# TrinketBlinkM0F.net
KiCad netlist of a schematic drawn in EAGLE
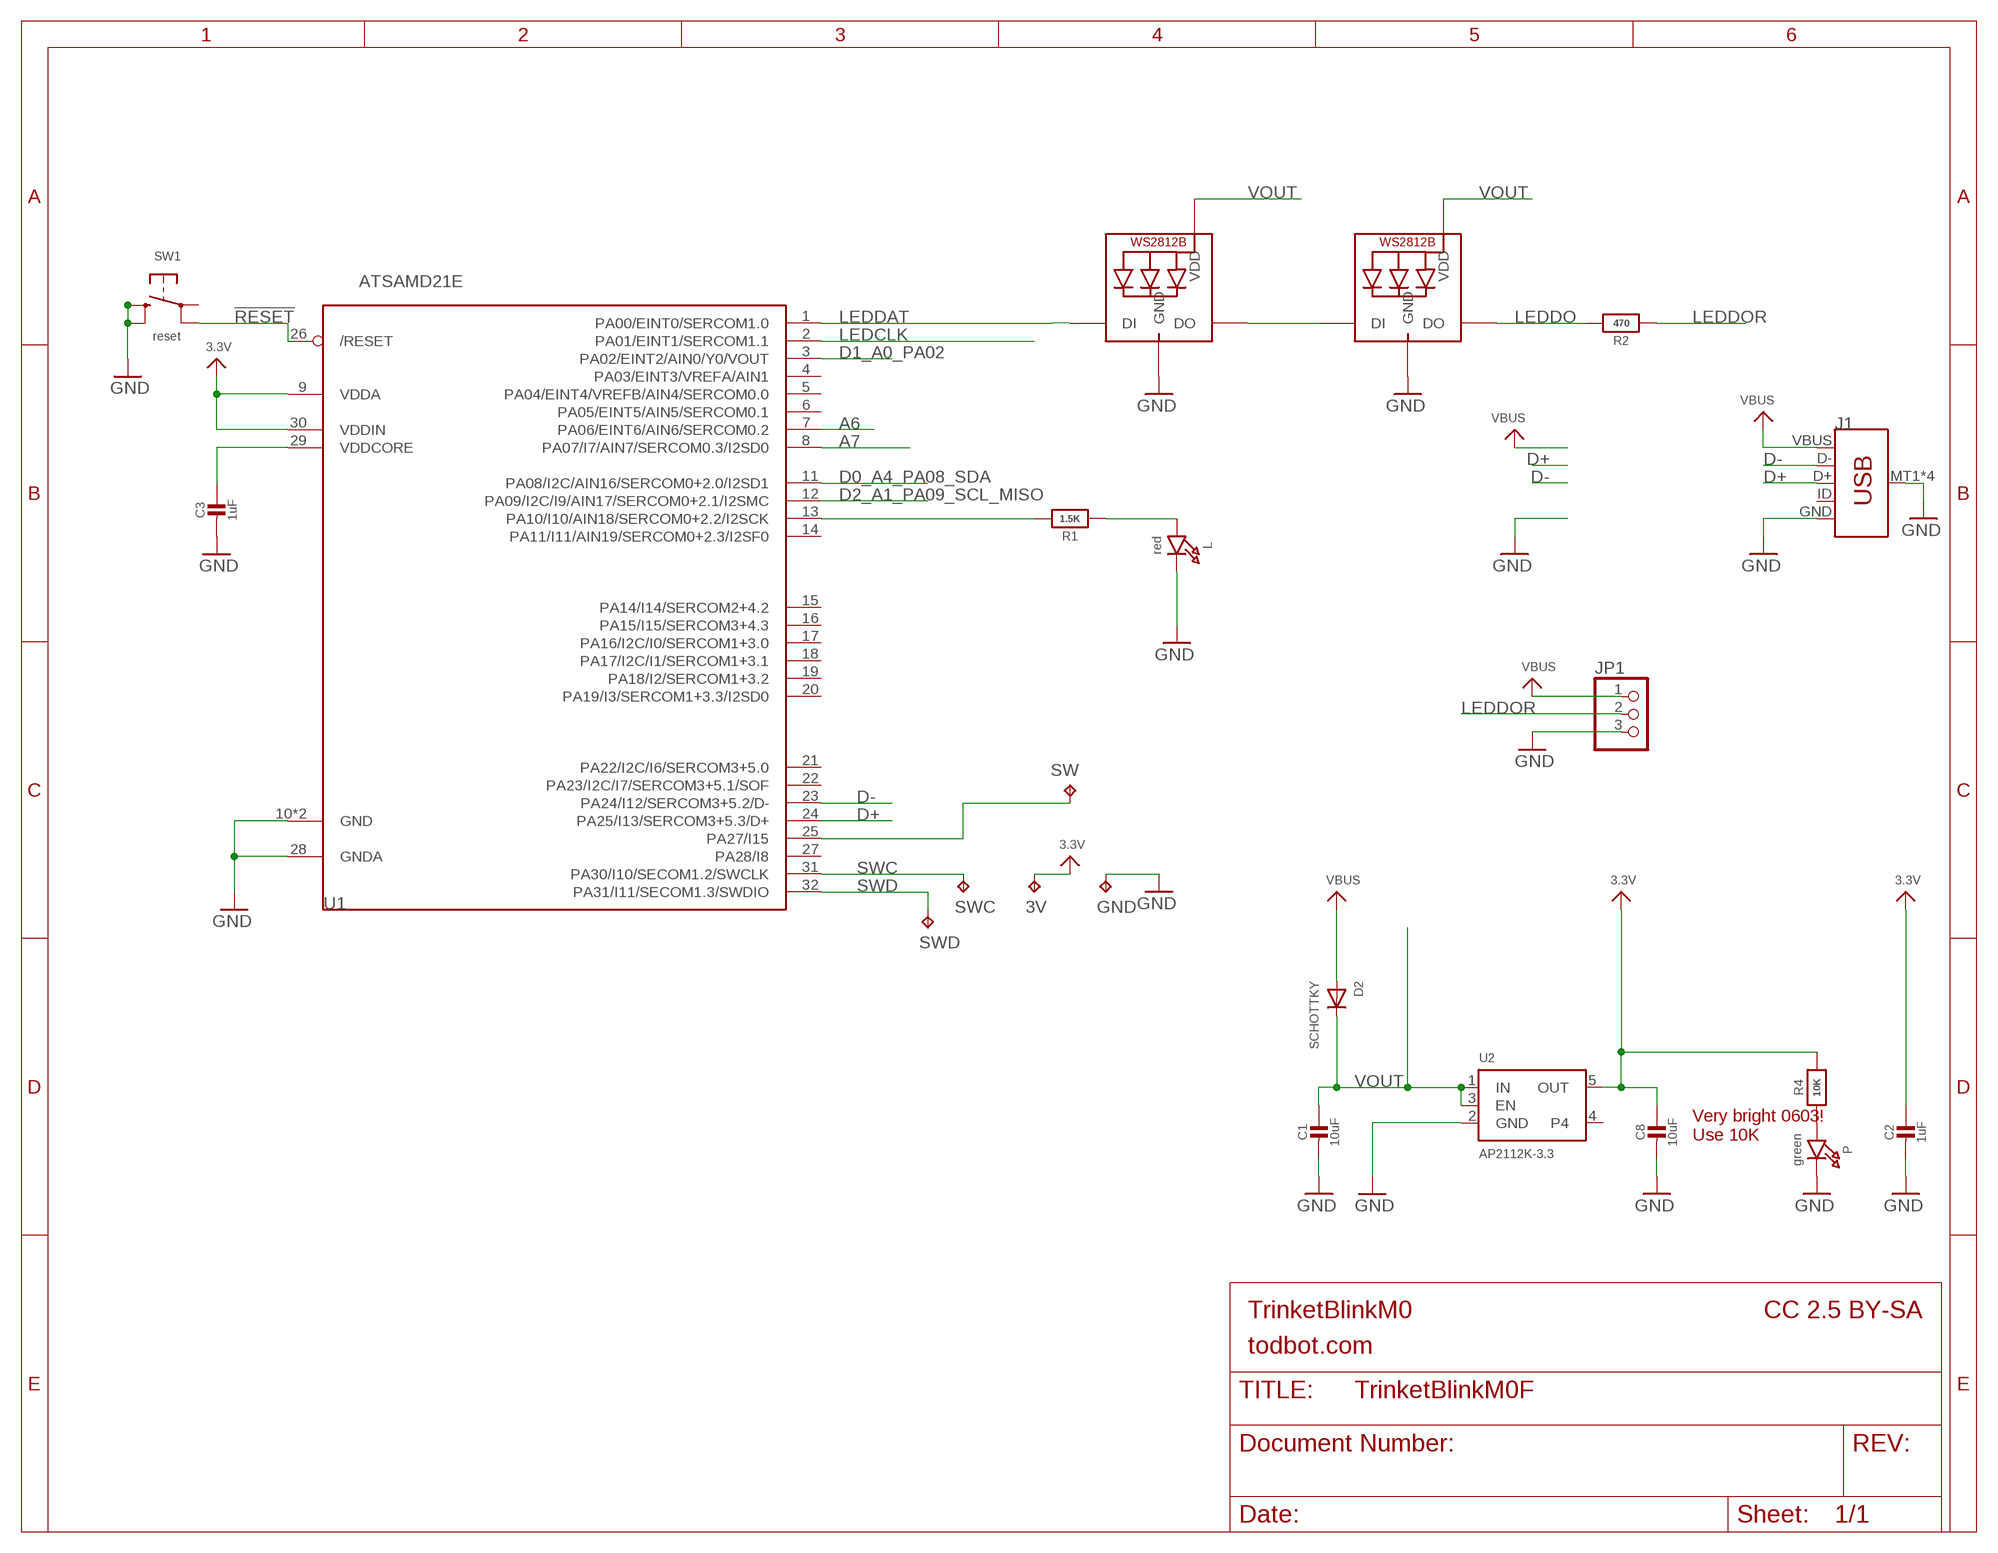
[diagram p0: schematic, sheet 1]

(export (version "E")
  (design (tool "Eeschema 10.0.6"))
  (components
    (comp (ref "3V")
      (value "TPB1,27")
      (footprint "eagle-import:B1,27")
      (libsource (lib "eagle-import") (part "TPB1,27"))
    )
    (comp (ref "C1")
      (value "10uF")
      (footprint "eagle-import:0805-NO")
      (libsource (lib "eagle-import") (part "CAP_CERAMIC0805-NOOUTLINE"))
    )
    (comp (ref "C2")
      (value "1uF")
      (footprint "eagle-import:0603-NO")
      (libsource (lib "eagle-import") (part "CAP_CERAMIC0603_NO"))
    )
    (comp (ref "C3")
      (value "1uF")
      (footprint "eagle-import:0603-NO")
      (libsource (lib "eagle-import") (part "CAP_CERAMIC0603_NO"))
    )
    (comp (ref "C8")
      (value "10uF")
      (footprint "eagle-import:0805-NO")
      (libsource (lib "eagle-import") (part "CAP_CERAMIC0805-NOOUTLINE"))
    )
    (comp (ref "D2")
      (value "SCHOTTKY")
      (footprint "eagle-import:SOD-123FL")
      (libsource (lib "eagle-import") (part "DIODE_SOD-123FL"))
    )
    (comp (ref "GND")
      (value "TPB1,27")
      (footprint "eagle-import:B1,27")
      (libsource (lib "eagle-import") (part "TPB1,27"))
    )
    (comp (ref "J1")
      (value "USB_MICRO-B_SMT")
      (footprint "eagle-import:USB-MICROB")
      (libsource (lib "eagle-import") (part "USB_MICRO-B_SMT"))
    )
    (comp (ref "JP1")
      (value "PINHD-1X3CB")
      (footprint "eagle-import:1X03-CLEANBIG")
      (libsource (lib "eagle-import") (part "PINHD-1X3CB"))
    )
    (comp (ref "L")
      (value "red")
      (footprint "eagle-import:CHIPLED_0603_NOOUTLINE")
      (libsource (lib "eagle-import") (part "LED0603_NOOUTLINE"))
    )
    (comp (ref "LED1")
      (value "WS2812B_5050N")
      (footprint "eagle-import:WS2812B-NARROW")
      (libsource (lib "eagle-import") (part "WS2812B_5050N"))
    )
    (comp (ref "LED2")
      (value "WS2812B_5050N")
      (footprint "eagle-import:WS2812B-NARROW")
      (libsource (lib "eagle-import") (part "WS2812B_5050N"))
    )
    (comp (ref "P")
      (value "green")
      (footprint "eagle-import:CHIPLED_0603_NOOUTLINE")
      (libsource (lib "eagle-import") (part "LED0603_NOOUTLINE"))
    )
    (comp (ref "R1")
      (value "1.5K")
      (footprint "eagle-import:0603-NO")
      (libsource (lib "eagle-import") (part "RESISTOR_0603_NOOUT"))
    )
    (comp (ref "R2")
      (value "470")
      (footprint "eagle-import:0603-NO")
      (libsource (lib "eagle-import") (part "RESISTOR_0603_NOOUT"))
    )
    (comp (ref "R4")
      (value "10K")
      (footprint "eagle-import:0603-NO")
      (libsource (lib "eagle-import") (part "RESISTOR_0603_NOOUT"))
    )
    (comp (ref "SW")
      (value "TPB1,27")
      (footprint "eagle-import:B1,27")
      (libsource (lib "eagle-import") (part "TPB1,27"))
    )
    (comp (ref "SW1")
      (value "reset")
      (footprint "eagle-import:BTN_KMR2_4.6X2.8")
      (libsource (lib "eagle-import") (part "SWITCH_TACT_SMT4.6X2.8"))
    )
    (comp (ref "SWC")
      (value "TPB1,27")
      (footprint "eagle-import:B1,27")
      (libsource (lib "eagle-import") (part "TPB1,27"))
    )
    (comp (ref "SWD")
      (value "TPB1,27")
      (footprint "eagle-import:B1,27")
      (libsource (lib "eagle-import") (part "TPB1,27"))
    )
    (comp (ref "U1")
      (value "ATSAMD21E")
      (footprint "eagle-import:QFN32_5MM")
      (libsource (lib "eagle-import") (part "ATSAMD21E"))
    )
    (comp (ref "U2")
      (value "AP2112K-3.3")
      (footprint "eagle-import:SOT23-5")
      (libsource (lib "eagle-import") (part "VREG_SOT23-5"))
    )
  )
  (nets
    (net (code "1") (name "/A6") (class "Default")
      (node (ref "U1") (pin "7") (pinfunction "PA06/EINT6/AIN6/SERCOM0.2_7") (pintype "bidirectional"))
    )
    (net (code "2") (name "/A7") (class "Default")
      (node (ref "U1") (pin "8") (pinfunction "PA07/I7/AIN7/SERCOM0.3/I2SD0_8") (pintype "bidirectional"))
    )
    (net (code "3") (name "/D+") (class "Default")
      (node (ref "J1") (pin "D+") (pinfunction "D+_D+") (pintype "bidirectional"))
      (node (ref "U1") (pin "24") (pinfunction "PA25/I13/SERCOM3+5.3/D+_24") (pintype "bidirectional"))
    )
    (net (code "4") (name "/D-") (class "Default")
      (node (ref "J1") (pin "D-") (pinfunction "D-_D-") (pintype "bidirectional"))
      (node (ref "U1") (pin "23") (pinfunction "PA24/I12/SERCOM3+5.2/D-_23") (pintype "bidirectional"))
    )
    (net (code "5") (name "/D0_A4_PA08_SDA") (class "Default")
      (node (ref "U1") (pin "11") (pinfunction "PA08/I2C/AIN16/SERCOM0+2.0/I2SD1_11") (pintype "bidirectional"))
    )
    (net (code "6") (name "/D1_A0_PA02") (class "Default")
      (node (ref "U1") (pin "3") (pinfunction "PA02/EINT2/AIN0/Y0/VOUT_3") (pintype "bidirectional"))
    )
    (net (code "7") (name "/D2_A1_PA09_SCL_MISO") (class "Default")
      (node (ref "U1") (pin "12") (pinfunction "PA09/I2C/I9/AIN17/SERCOM0+2.1/I2SMC_12") (pintype "bidirectional"))
    )
    (net (code "8") (name "/LEDCLK") (class "Default")
      (node (ref "U1") (pin "2") (pinfunction "PA01/EINT1/SERCOM1.1_2") (pintype "bidirectional"))
    )
    (net (code "9") (name "/LEDDAT") (class "Default")
      (node (ref "LED1") (pin "4-DIN") (pinfunction "DI_4-DIN") (pintype "input"))
      (node (ref "U1") (pin "1") (pinfunction "PA00/EINT0/SERCOM1.0_1") (pintype "bidirectional"))
    )
    (net (code "10") (name "/LEDDO") (class "Default")
      (node (ref "LED2") (pin "2-DOUT") (pinfunction "DO_2-DOUT") (pintype "output"))
      (node (ref "R2") (pin "2") (pinfunction "2_2") (pintype "passive"))
    )
    (net (code "11") (name "/LEDDOR") (class "Default")
      (node (ref "JP1") (pin "2") (pinfunction "2_2") (pintype "passive"))
      (node (ref "R2") (pin "1") (pinfunction "1_1") (pintype "passive"))
    )
    (net (code "12") (name "/SWC") (class "Default")
      (node (ref "SWC") (pin "TP") (pinfunction "TP_TP") (pintype "input"))
      (node (ref "U1") (pin "31") (pinfunction "PA30/I10/SECOM1.2/SWCLK_31") (pintype "bidirectional"))
    )
    (net (code "13") (name "/SWD") (class "Default")
      (node (ref "SWD") (pin "TP") (pinfunction "TP_TP") (pintype "input"))
      (node (ref "U1") (pin "32") (pinfunction "PA31/I11/SECOM1.3/SWDIO_32") (pintype "bidirectional"))
    )
    (net (code "14") (name "/VOUT") (class "Default")
      (node (ref "C1") (pin "1") (pinfunction "1_1") (pintype "passive"))
      (node (ref "D2") (pin "C") (pinfunction "C_C") (pintype "passive"))
      (node (ref "LED1") (pin "1-VDD") (pinfunction "VDD_1-VDD") (pintype "power_in"))
      (node (ref "LED2") (pin "1-VDD") (pinfunction "VDD_1-VDD") (pintype "power_in"))
      (node (ref "U2") (pin "1") (pinfunction "IN_1") (pintype "power_in"))
      (node (ref "U2") (pin "3") (pinfunction "EN_3") (pintype "input"))
    )
    (net (code "15") (name "/~{RESET}") (class "Default")
      (node (ref "SW1") (pin "A'") (pinfunction "P1_A'") (pintype "passive"))
      (node (ref "U1") (pin "26") (pinfunction "/RESET_26") (pintype "bidirectional"))
    )
    (net (code "16") (name "3.3V") (class "Default")
      (node (ref "3V") (pin "TP") (pinfunction "TP_TP") (pintype "input"))
      (node (ref "C2") (pin "1") (pinfunction "1_1") (pintype "passive"))
      (node (ref "C8") (pin "1") (pinfunction "1_1") (pintype "passive"))
      (node (ref "R4") (pin "2") (pinfunction "2_2") (pintype "passive"))
      (node (ref "U1") (pin "30") (pinfunction "VDDIN_30") (pintype "power_in"))
      (node (ref "U1") (pin "9") (pinfunction "VDDA_9") (pintype "power_in"))
      (node (ref "U2") (pin "5") (pinfunction "OUT_5") (pintype "power_in"))
    )
    (net (code "17") (name "GND") (class "Default")
      (node (ref "C1") (pin "2") (pinfunction "2_2") (pintype "passive"))
      (node (ref "C2") (pin "2") (pinfunction "2_2") (pintype "passive"))
      (node (ref "C3") (pin "2") (pinfunction "2_2") (pintype "passive"))
      (node (ref "C8") (pin "2") (pinfunction "2_2") (pintype "passive"))
      (node (ref "GND") (pin "TP") (pinfunction "TP_TP") (pintype "input"))
      (node (ref "J1") (pin "GND") (pinfunction "GND_GND") (pintype "power_in"))
      (node (ref "J1") (pin "MT1") (pinfunction "SHIELD_MT1") (pintype "bidirectional"))
      (node (ref "J1") (pin "MT2") (pinfunction "SHIELD_MT2") (pintype "bidirectional"))
      (node (ref "J1") (pin "P$1") (pinfunction "SHIELD_P$1") (pintype "bidirectional"))
      (node (ref "J1") (pin "P$2") (pinfunction "SHIELD_P$2") (pintype "bidirectional"))
      (node (ref "JP1") (pin "3") (pinfunction "3_3") (pintype "passive"))
      (node (ref "L") (pin "C") (pinfunction "C_C") (pintype "passive"))
      (node (ref "LED1") (pin "3-GND") (pinfunction "GND_3-GND") (pintype "power_in"))
      (node (ref "LED2") (pin "3-GND") (pinfunction "GND_3-GND") (pintype "power_in"))
      (node (ref "P") (pin "C") (pinfunction "C_C") (pintype "passive"))
      (node (ref "SW1") (pin "B") (pinfunction "S_B") (pintype "passive"))
      (node (ref "SW1") (pin "B'") (pinfunction "S1_B'") (pintype "passive"))
      (node (ref "U1") (pin "10") (pinfunction "GND_10") (pintype "power_in"))
      (node (ref "U1") (pin "28") (pinfunction "GNDA_28") (pintype "power_in"))
      (node (ref "U1") (pin "33") (pinfunction "GND_33") (pintype "power_in"))
      (node (ref "U2") (pin "2") (pinfunction "GND_2") (pintype "power_in"))
    )
    (net (code "18") (name "Net-(L-PadA)") (class "Default")
      (node (ref "L") (pin "A") (pinfunction "A_A") (pintype "passive"))
      (node (ref "R1") (pin "1") (pinfunction "1_1") (pintype "passive"))
    )
    (net (code "19") (name "Net-(LED1-DO)") (class "Default")
      (node (ref "LED1") (pin "2-DOUT") (pinfunction "DO_2-DOUT") (pintype "output"))
      (node (ref "LED2") (pin "4-DIN") (pinfunction "DI_4-DIN") (pintype "input"))
    )
    (net (code "20") (name "Net-(P-PadA)") (class "Default")
      (node (ref "P") (pin "A") (pinfunction "A_A") (pintype "passive"))
      (node (ref "R4") (pin "1") (pinfunction "1_1") (pintype "passive"))
    )
    (net (code "21") (name "Net-(U1-PA10{slash}I10{slash}AIN18{slash}SERCOM0+2.2{slash}I2SCK)") (class "Default")
      (node (ref "R1") (pin "2") (pinfunction "2_2") (pintype "passive"))
      (node (ref "U1") (pin "13") (pinfunction "PA10/I10/AIN18/SERCOM0+2.2/I2SCK_13") (pintype "bidirectional"))
    )
    (net (code "22") (name "Net-(U1-PA27{slash}I15)") (class "Default")
      (node (ref "SW") (pin "TP") (pinfunction "TP_TP") (pintype "input"))
      (node (ref "U1") (pin "25") (pinfunction "PA27/I15_25") (pintype "bidirectional"))
    )
    (net (code "23") (name "Net-(U1-VDDCORE)") (class "Default")
      (node (ref "C3") (pin "1") (pinfunction "1_1") (pintype "passive"))
      (node (ref "U1") (pin "29") (pinfunction "VDDCORE_29") (pintype "power_in"))
    )
    (net (code "24") (name "VBUS") (class "Default")
      (node (ref "D2") (pin "A") (pinfunction "A_A") (pintype "passive"))
      (node (ref "J1") (pin "VBUS") (pinfunction "VBUS_VBUS") (pintype "power_in"))
      (node (ref "JP1") (pin "1") (pinfunction "1_1") (pintype "passive"))
    )
    (net (code "25") (name "unconnected-(J1-PadID)") (class "Default")
      (node (ref "J1") (pin "ID") (pinfunction "ID_ID") (pintype "bidirectional"))
    )
    (net (code "26") (name "unconnected-(SW1-P-PadA)") (class "Default")
      (node (ref "SW1") (pin "A") (pinfunction "P_A") (pintype "passive"))
    )
    (net (code "27") (name "unconnected-(U1-PA03{slash}EINT3{slash}VREFA{slash}AIN1-Pad4)") (class "Default")
      (node (ref "U1") (pin "4") (pinfunction "PA03/EINT3/VREFA/AIN1_4") (pintype "bidirectional"))
    )
    (net (code "28") (name "unconnected-(U1-PA04{slash}EINT4{slash}VREFB{slash}AIN4{slash}SERCOM0.0-Pad5)") (class "Default")
      (node (ref "U1") (pin "5") (pinfunction "PA04/EINT4/VREFB/AIN4/SERCOM0.0_5") (pintype "bidirectional"))
    )
    (net (code "29") (name "unconnected-(U1-PA05{slash}EINT5{slash}AIN5{slash}SERCOM0.1-Pad6)") (class "Default")
      (node (ref "U1") (pin "6") (pinfunction "PA05/EINT5/AIN5/SERCOM0.1_6") (pintype "bidirectional"))
    )
    (net (code "30") (name "unconnected-(U1-PA11{slash}I11{slash}AIN19{slash}SERCOM0+2.3{slash}I2SF0-Pad14)") (class "Default")
      (node (ref "U1") (pin "14") (pinfunction "PA11/I11/AIN19/SERCOM0+2.3/I2SF0_14") (pintype "bidirectional"))
    )
    (net (code "31") (name "unconnected-(U1-PA14{slash}I14{slash}SERCOM2+4.2-Pad15)") (class "Default")
      (node (ref "U1") (pin "15") (pinfunction "PA14/I14/SERCOM2+4.2_15") (pintype "bidirectional"))
    )
    (net (code "32") (name "unconnected-(U1-PA15{slash}I15{slash}SERCOM3+4.3-Pad16)") (class "Default")
      (node (ref "U1") (pin "16") (pinfunction "PA15/I15/SERCOM3+4.3_16") (pintype "bidirectional"))
    )
    (net (code "33") (name "unconnected-(U1-PA16{slash}I2C{slash}I0{slash}SERCOM1+3.0-Pad17)") (class "Default")
      (node (ref "U1") (pin "17") (pinfunction "PA16/I2C/I0/SERCOM1+3.0_17") (pintype "bidirectional"))
    )
    (net (code "34") (name "unconnected-(U1-PA17{slash}I2C{slash}I1{slash}SERCOM1+3.1-Pad18)") (class "Default")
      (node (ref "U1") (pin "18") (pinfunction "PA17/I2C/I1/SERCOM1+3.1_18") (pintype "bidirectional"))
    )
    (net (code "35") (name "unconnected-(U1-PA18{slash}I2{slash}SERCOM1+3.2-Pad19)") (class "Default")
      (node (ref "U1") (pin "19") (pinfunction "PA18/I2/SERCOM1+3.2_19") (pintype "bidirectional"))
    )
    (net (code "36") (name "unconnected-(U1-PA19{slash}I3{slash}SERCOM1+3.3{slash}I2SD0-Pad20)") (class "Default")
      (node (ref "U1") (pin "20") (pinfunction "PA19/I3/SERCOM1+3.3/I2SD0_20") (pintype "bidirectional"))
    )
    (net (code "37") (name "unconnected-(U1-PA22{slash}I2C{slash}I6{slash}SERCOM3+5.0-Pad21)") (class "Default")
      (node (ref "U1") (pin "21") (pinfunction "PA22/I2C/I6/SERCOM3+5.0_21") (pintype "bidirectional"))
    )
    (net (code "38") (name "unconnected-(U1-PA23{slash}I2C{slash}I7{slash}SERCOM3+5.1{slash}SOF-Pad22)") (class "Default")
      (node (ref "U1") (pin "22") (pinfunction "PA23/I2C/I7/SERCOM3+5.1/SOF_22") (pintype "bidirectional"))
    )
    (net (code "39") (name "unconnected-(U1-PA28{slash}I8-Pad27)") (class "Default")
      (node (ref "U1") (pin "27") (pinfunction "PA28/I8_27") (pintype "bidirectional"))
    )
    (net (code "40") (name "unconnected-(U2-P4-Pad4)") (class "Default")
      (node (ref "U2") (pin "4") (pinfunction "P4_4") (pintype "bidirectional"))
    )
  )
)
